# space_elevator.net
KiCad netlist of a schematic drawn in EAGLE
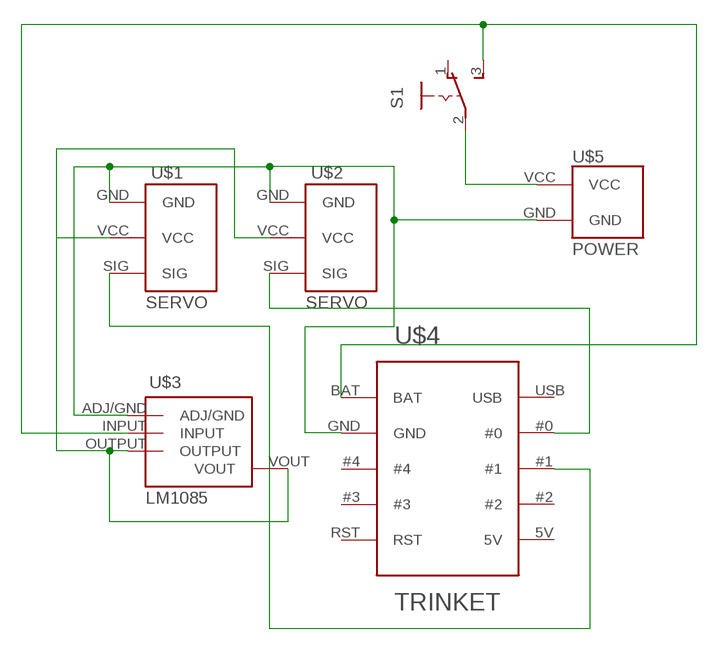
[diagram p0: schematic, sheet 1]

(export (version "E")
  (design (tool "Eeschema 10.0.6"))
  (components
    (comp (ref "S1")
      (value "255SB")
      (footprint "eagle-import:255SB")
      (libsource (lib "eagle-import") (part "255SB"))
    )
    (comp (ref "U$1")
      (value "SERVO")
      (footprint "eagle-import:SERVO")
      (libsource (lib "eagle-import") (part "SERVO"))
    )
    (comp (ref "U$2")
      (value "SERVO")
      (footprint "eagle-import:SERVO")
      (libsource (lib "eagle-import") (part "SERVO"))
    )
    (comp (ref "U$3")
      (value "LM1085")
      (footprint "eagle-import:TO220H")
      (libsource (lib "eagle-import") (part "LM1085"))
    )
    (comp (ref "U$4")
      (value "TRINKET")
      (footprint "eagle-import:TRINKETUSB")
      (libsource (lib "eagle-import") (part "TRINKET"))
    )
    (comp (ref "U$5")
      (value "POWER")
      (footprint "eagle-import:POWER")
      (libsource (lib "eagle-import") (part "POWER"))
    )
  )
  (nets
    (net (code "1") (name "Net-(S1-P)") (class "Default")
      (node (ref "S1") (pin "2") (pinfunction "P_2") (pintype "passive"))
      (node (ref "U$5") (pin "VCC") (pinfunction "VCC_VCC") (pintype "bidirectional"))
    )
    (net (code "2") (name "Net-(S1-S)") (class "Default")
      (node (ref "S1") (pin "3") (pinfunction "S_3") (pintype "passive"))
      (node (ref "U$3") (pin "INPUT") (pinfunction "INPUT_INPUT") (pintype "bidirectional"))
      (node (ref "U$4") (pin "BAT") (pinfunction "BAT_BAT") (pintype "bidirectional"))
    )
    (net (code "3") (name "Net-(U$1-PadGND)") (class "Default")
      (node (ref "U$1") (pin "GND") (pinfunction "GND_GND") (pintype "bidirectional"))
      (node (ref "U$2") (pin "GND") (pinfunction "GND_GND") (pintype "bidirectional"))
      (node (ref "U$3") (pin "ADJ/GND") (pinfunction "ADJ/GND_ADJ/GND") (pintype "bidirectional"))
      (node (ref "U$4") (pin "GND") (pinfunction "GND_GND") (pintype "bidirectional"))
      (node (ref "U$5") (pin "GND") (pinfunction "GND_GND") (pintype "bidirectional"))
    )
    (net (code "4") (name "Net-(U$1-PadSIG)") (class "Default")
      (node (ref "U$1") (pin "SIG") (pinfunction "SIG_SIG") (pintype "bidirectional"))
      (node (ref "U$4") (pin "#1") (pinfunction "#1_#1") (pintype "bidirectional"))
    )
    (net (code "5") (name "Net-(U$1-PadVCC)") (class "Default")
      (node (ref "U$1") (pin "VCC") (pinfunction "VCC_VCC") (pintype "bidirectional"))
      (node (ref "U$2") (pin "VCC") (pinfunction "VCC_VCC") (pintype "bidirectional"))
      (node (ref "U$3") (pin "OUTPUT") (pinfunction "OUTPUT_OUTPUT") (pintype "bidirectional"))
      (node (ref "U$3") (pin "VOUT") (pinfunction "VOUT_VOUT") (pintype "bidirectional"))
    )
    (net (code "6") (name "Net-(U$2-PadSIG)") (class "Default")
      (node (ref "U$2") (pin "SIG") (pinfunction "SIG_SIG") (pintype "bidirectional"))
      (node (ref "U$4") (pin "#0") (pinfunction "#0_#0") (pintype "bidirectional"))
    )
    (net (code "7") (name "unconnected-(S1-O-Pad1)") (class "Default")
      (node (ref "S1") (pin "1") (pinfunction "O_1") (pintype "passive"))
    )
    (net (code "8") (name "unconnected-(U$4-Pad#2)") (class "Default")
      (node (ref "U$4") (pin "#2") (pinfunction "#2_#2") (pintype "bidirectional"))
    )
    (net (code "9") (name "unconnected-(U$4-Pad#3)") (class "Default")
      (node (ref "U$4") (pin "#3") (pinfunction "#3_#3") (pintype "bidirectional"))
    )
    (net (code "10") (name "unconnected-(U$4-Pad#4)") (class "Default")
      (node (ref "U$4") (pin "#4") (pinfunction "#4_#4") (pintype "bidirectional"))
    )
    (net (code "11") (name "unconnected-(U$4-Pad5V)") (class "Default")
      (node (ref "U$4") (pin "5V") (pinfunction "5V_5V") (pintype "bidirectional"))
    )
    (net (code "12") (name "unconnected-(U$4-PadRST)") (class "Default")
      (node (ref "U$4") (pin "RST") (pinfunction "RST_RST") (pintype "bidirectional"))
    )
    (net (code "13") (name "unconnected-(U$4-PadUSB)") (class "Default")
      (node (ref "U$4") (pin "USB") (pinfunction "USB_USB") (pintype "bidirectional"))
    )
  )
)
